# AST1029.net
KiCad netlist of a schematic drawn in EAGLE
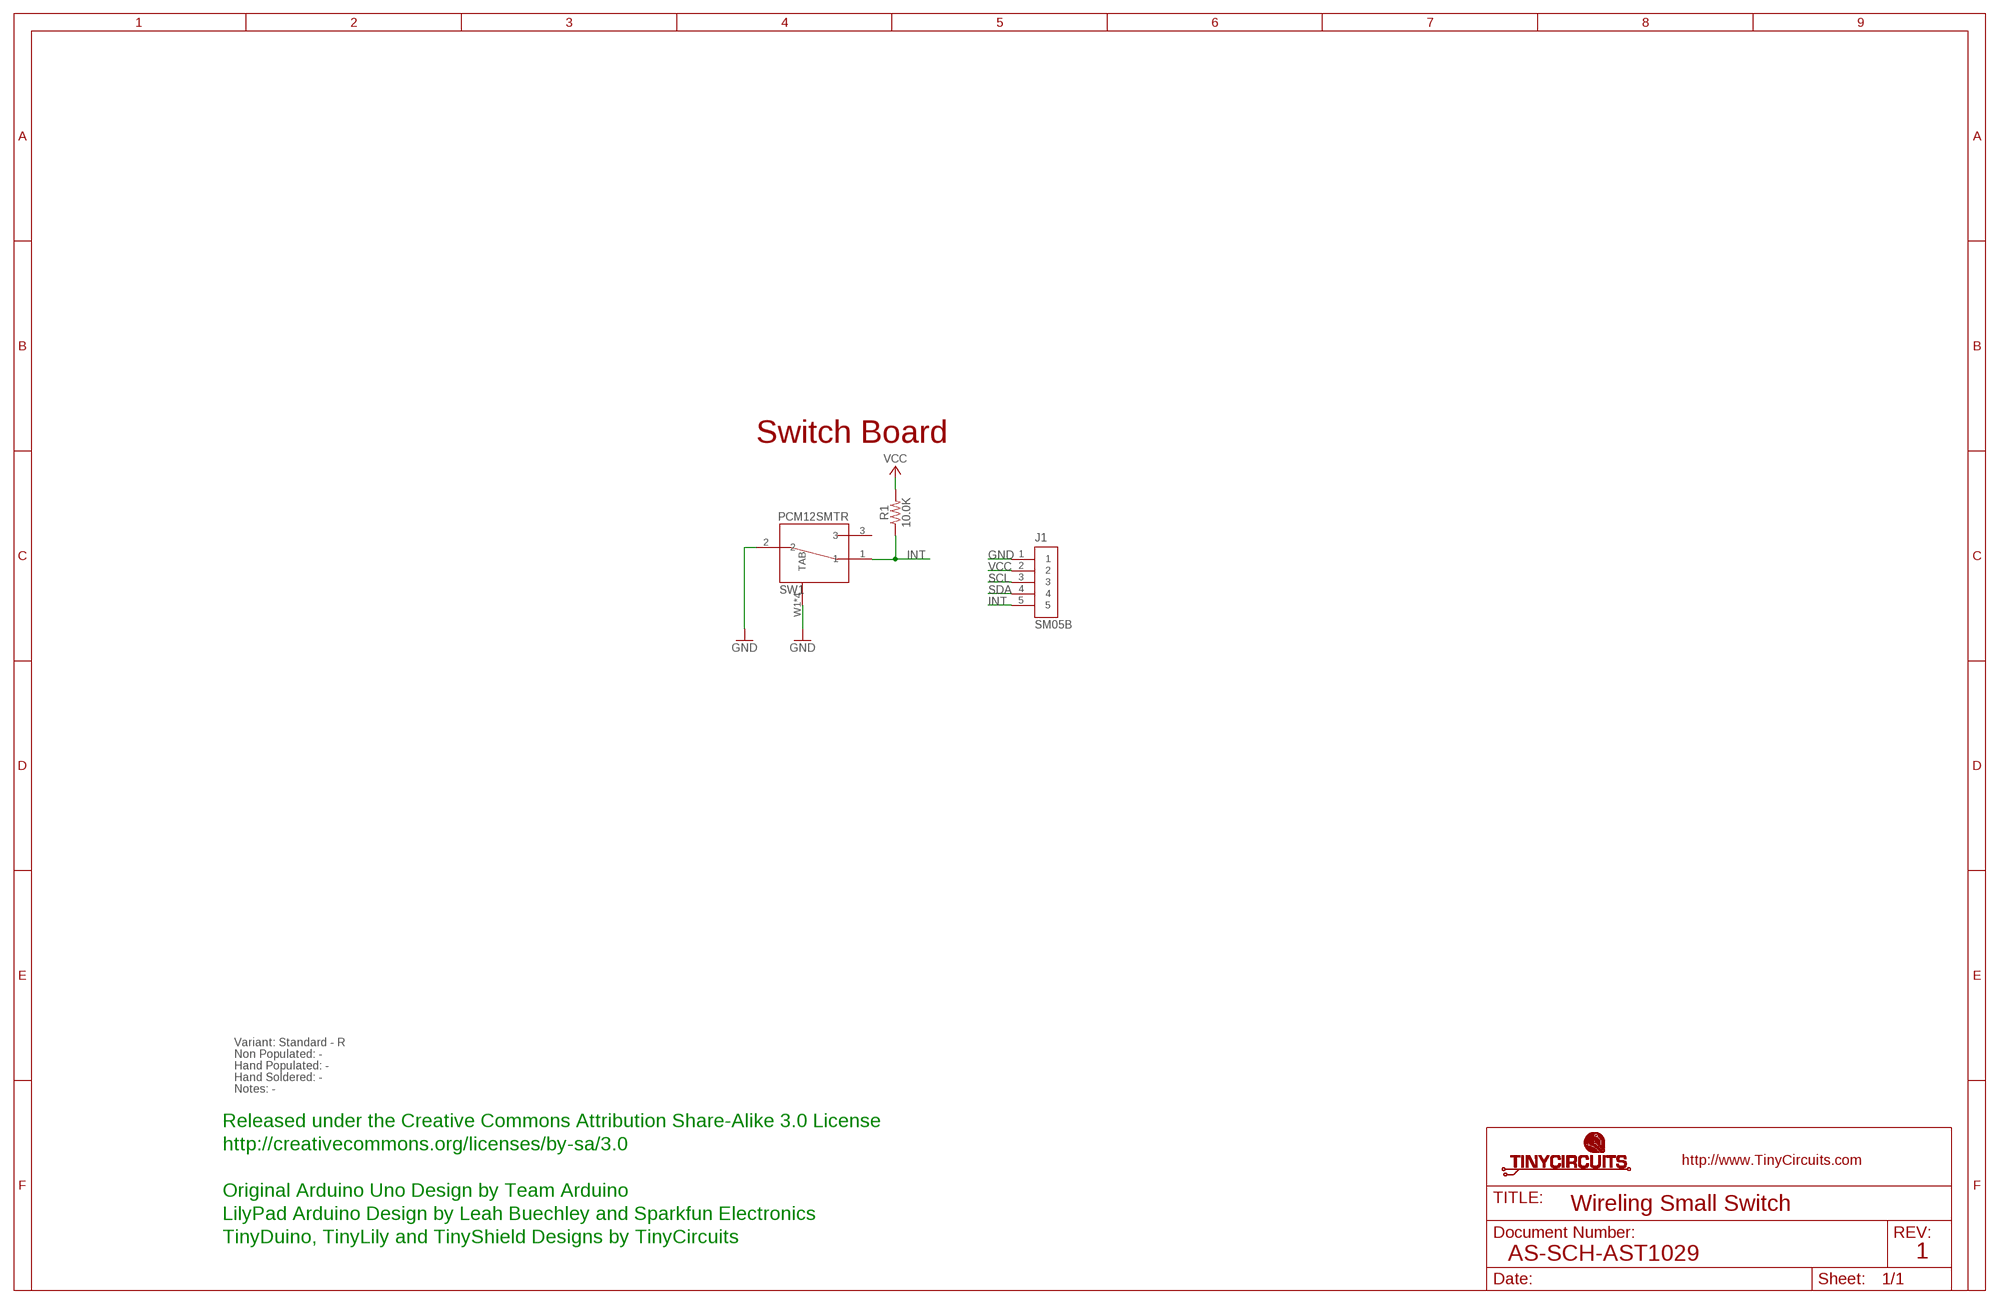
[diagram p0: schematic, sheet 1]

(export (version "E")
  (design (tool "Eeschema 10.0.6"))
  (components
    (comp (ref "J1")
      (value "SM05B")
      (footprint "eagle-import:JST_SH_5X1_EDGE")
      (fields (field (name "PARTNO") "AS-ITM-00340"))
      (libsource (lib "eagle-import") (part "AS-ITM-00340EDGE"))
    )
    (comp (ref "R1")
      (value "10.0K")
      (footprint "eagle-import:0402")
      (fields (field (name "PARTNO") "AS-ITM-00032"))
      (libsource (lib "eagle-import") (part "AS-ITM-00032"))
    )
    (comp (ref "SW1")
      (value "PCM12SMTR")
      (footprint "eagle-import:PCM12SMTR")
      (fields (field (name "PARTNO") "AS-ITM-00220"))
      (libsource (lib "eagle-import") (part "AS-ITM-00220"))
    )
  )
  (nets
    (net (code "1") (name "/INT") (class "Default")
      (node (ref "J1") (pin "5") (pinfunction "5_5") (pintype "bidirectional"))
      (node (ref "R1") (pin "1") (pinfunction "1_1") (pintype "passive"))
      (node (ref "SW1") (pin "1") (pinfunction "1_1") (pintype "bidirectional"))
    )
    (net (code "2") (name "/SCL") (class "Default")
      (node (ref "J1") (pin "3") (pinfunction "3_3") (pintype "bidirectional"))
    )
    (net (code "3") (name "/SDA") (class "Default")
      (node (ref "J1") (pin "4") (pinfunction "4_4") (pintype "bidirectional"))
    )
    (net (code "4") (name "GND") (class "Default")
      (node (ref "J1") (pin "1") (pinfunction "1_1") (pintype "bidirectional"))
      (node (ref "SW1") (pin "2") (pinfunction "2_2") (pintype "bidirectional"))
      (node (ref "SW1") (pin "W1") (pinfunction "TAB_W1") (pintype "bidirectional"))
      (node (ref "SW1") (pin "W2") (pinfunction "TAB_W2") (pintype "bidirectional"))
      (node (ref "SW1") (pin "W3") (pinfunction "TAB_W3") (pintype "bidirectional"))
      (node (ref "SW1") (pin "W4") (pinfunction "TAB_W4") (pintype "bidirectional"))
    )
    (net (code "5") (name "VCC") (class "Default")
      (node (ref "J1") (pin "2") (pinfunction "2_2") (pintype "bidirectional"))
      (node (ref "R1") (pin "2") (pinfunction "2_2") (pintype "passive"))
    )
    (net (code "6") (name "unconnected-(SW1-Pad3)") (class "Default")
      (node (ref "SW1") (pin "3") (pinfunction "3_3") (pintype "bidirectional"))
    )
  )
)
